# schematic.net
KiCad netlist of a schematic drawn in EasyEDA
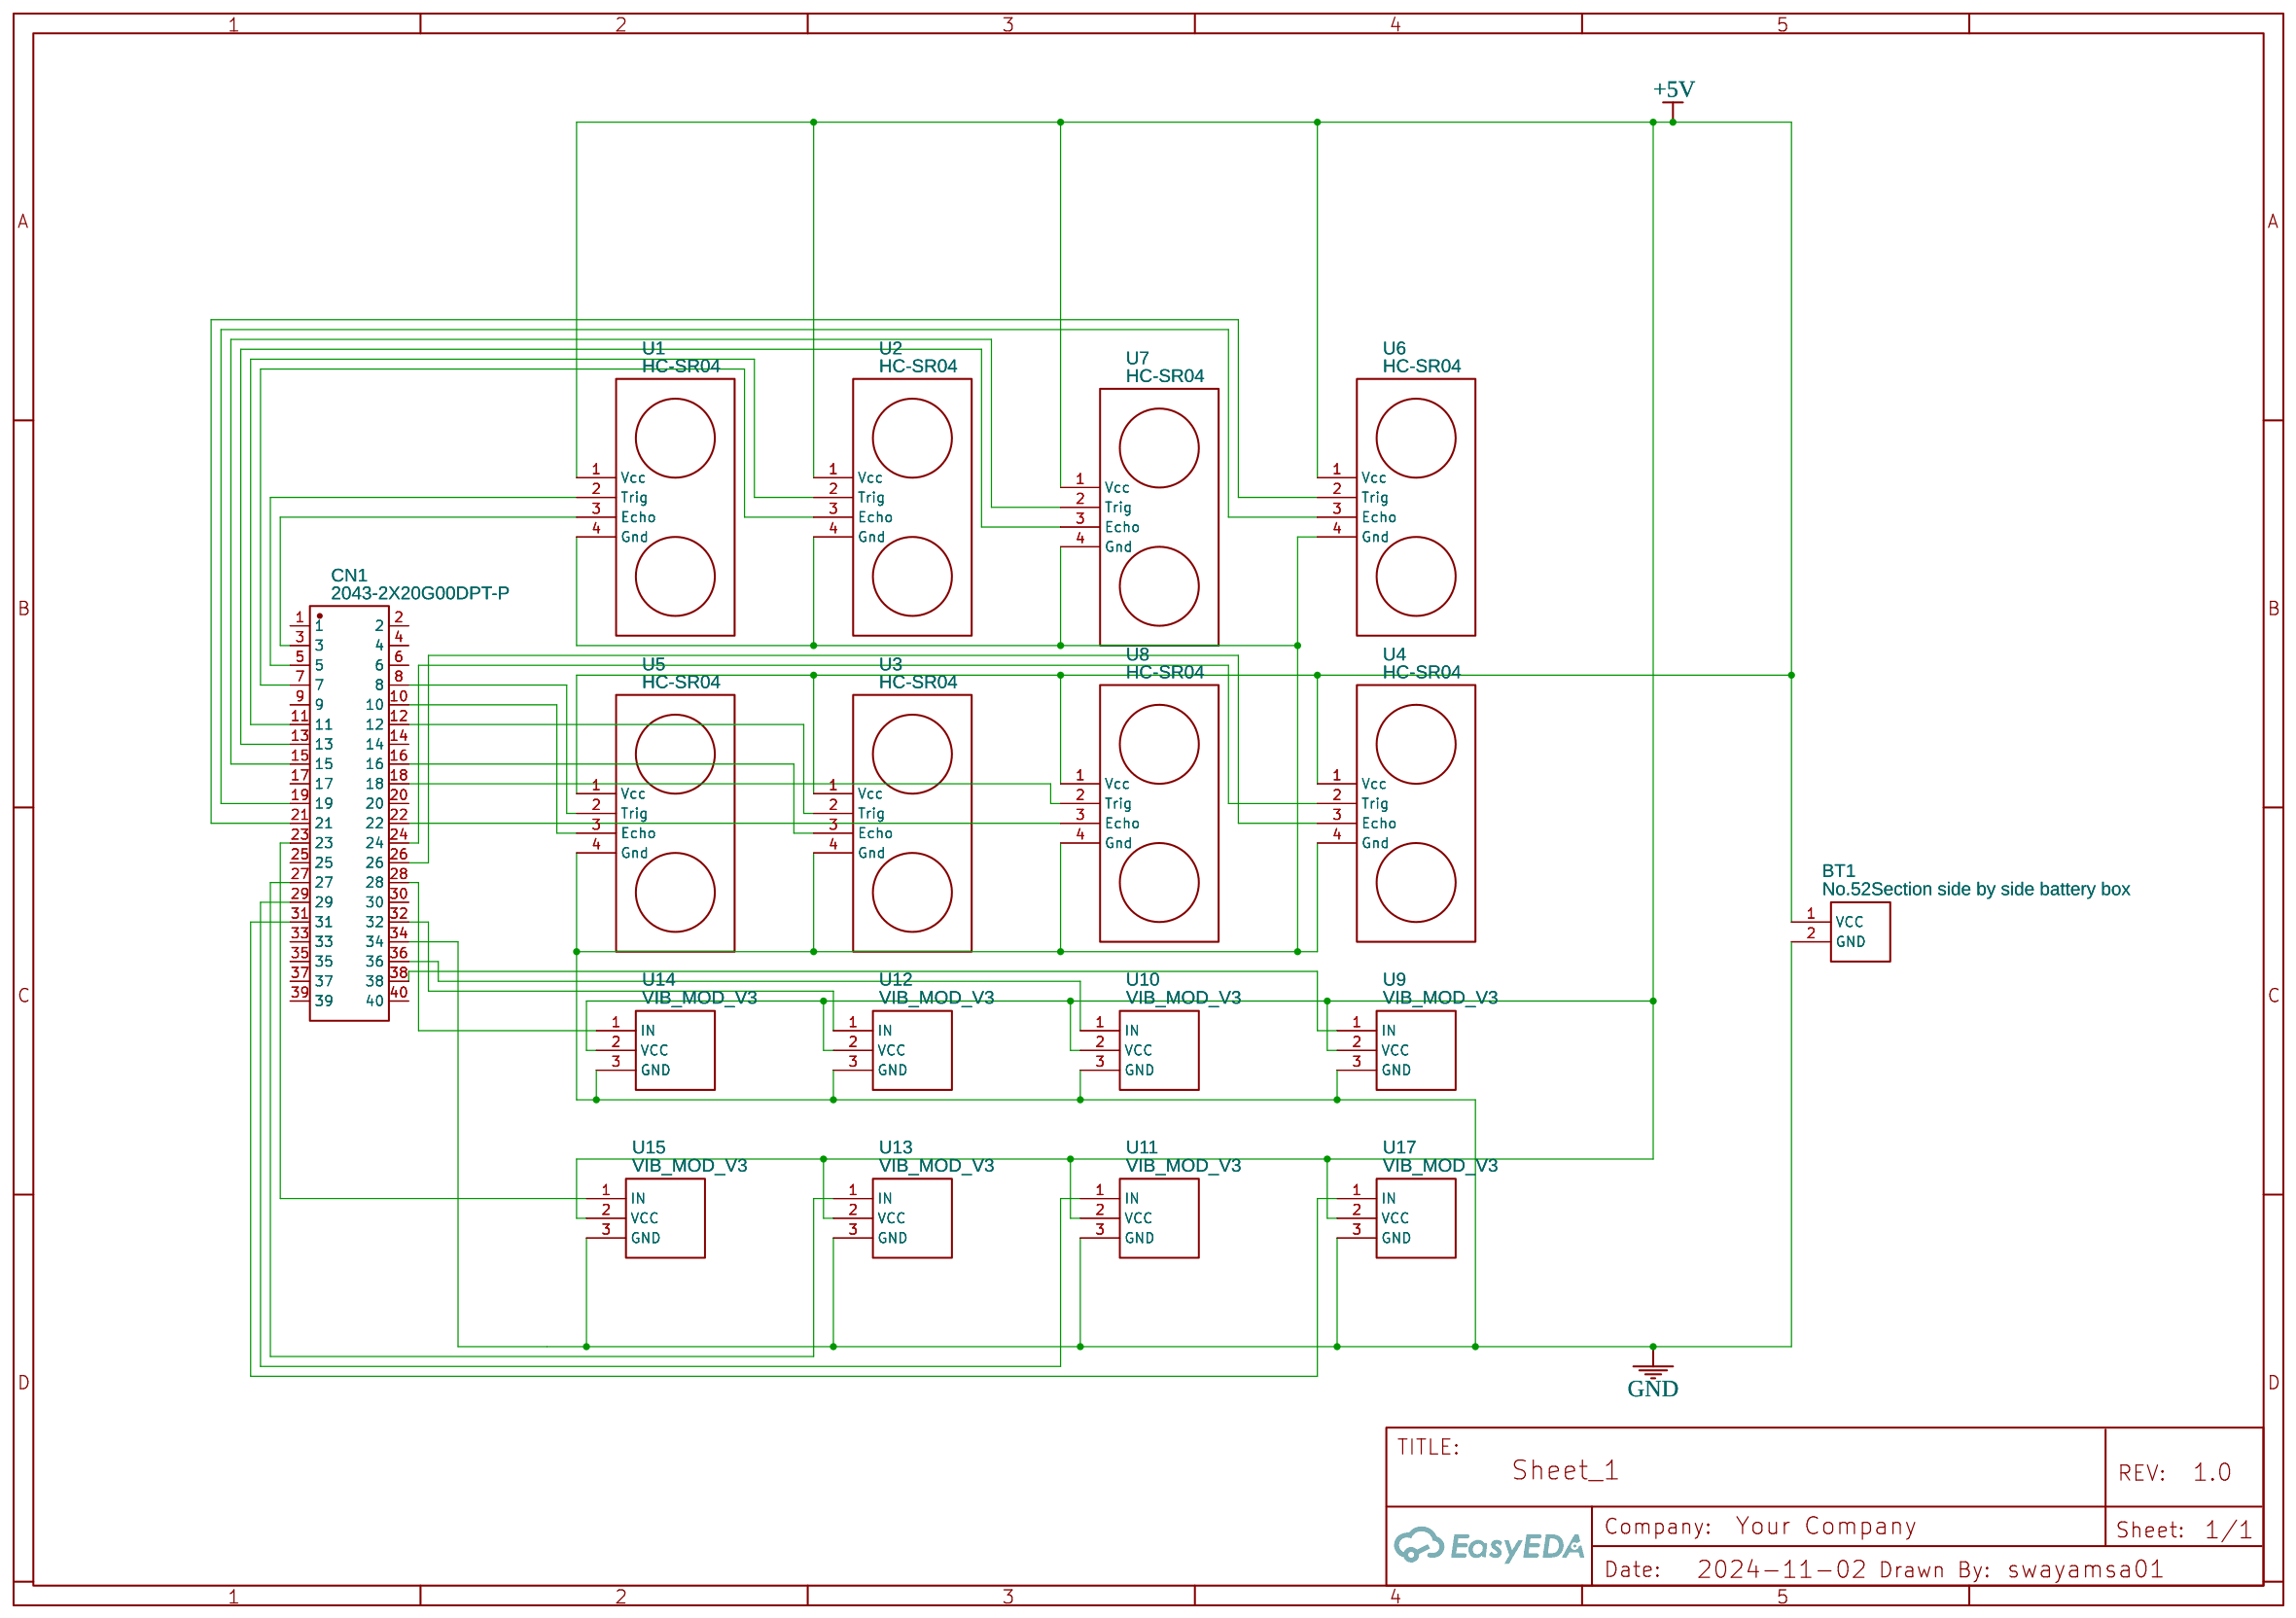
[diagram p0: schematic sheet]

(export (version "E")
  (design (tool "Eeschema 10.0.6"))
  (components
    (comp (ref "BT1")
      (value "No.52Section side by side battery box")
      (fields (field (name "Manufacturer Part") "五号2节并列电池盒") (field (name "Manufacturer") "国产"))
      (libsource (lib "") (part "No.52Section side by side battery box"))
    )
    (comp (ref "CN1") (value "2043-2X20G00DPT-P") (libsource (lib "") (part "2043-2X20G00DPT-P")))
    (comp (ref "U1") (value "HC-SR04") (libsource (lib "") (part "HC-SR04")))
    (comp (ref "U2") (value "HC-SR04") (libsource (lib "") (part "HC-SR04")))
    (comp (ref "U3") (value "HC-SR04") (libsource (lib "") (part "HC-SR04")))
    (comp (ref "U4") (value "HC-SR04") (libsource (lib "") (part "HC-SR04")))
    (comp (ref "U5") (value "HC-SR04") (libsource (lib "") (part "HC-SR04")))
    (comp (ref "U6") (value "HC-SR04") (libsource (lib "") (part "HC-SR04")))
    (comp (ref "U7") (value "HC-SR04") (libsource (lib "") (part "HC-SR04")))
    (comp (ref "U8") (value "HC-SR04") (libsource (lib "") (part "HC-SR04")))
    (comp (ref "U9") (value "VIB_MOD_V3") (libsource (lib "") (part "VIB_MOD_V3")))
    (comp (ref "U10") (value "VIB_MOD_V3") (libsource (lib "") (part "VIB_MOD_V3")))
    (comp (ref "U11") (value "VIB_MOD_V3") (libsource (lib "") (part "VIB_MOD_V3")))
    (comp (ref "U12") (value "VIB_MOD_V3") (libsource (lib "") (part "VIB_MOD_V3")))
    (comp (ref "U13") (value "VIB_MOD_V3") (libsource (lib "") (part "VIB_MOD_V3")))
    (comp (ref "U14") (value "VIB_MOD_V3") (libsource (lib "") (part "VIB_MOD_V3")))
    (comp (ref "U15") (value "VIB_MOD_V3") (libsource (lib "") (part "VIB_MOD_V3")))
    (comp (ref "U17") (value "VIB_MOD_V3") (libsource (lib "") (part "VIB_MOD_V3")))
  )
  (nets
    (net (code "1") (name "+5V") (class "Default")
      (node (ref "BT1") (pin "1") (pinfunction "VCC_1") (pintype "unspecified"))
      (node (ref "U1") (pin "1") (pinfunction "Vcc_1") (pintype "unspecified"))
      (node (ref "U10") (pin "2") (pinfunction "VCC_2") (pintype "unspecified"))
      (node (ref "U11") (pin "2") (pinfunction "VCC_2") (pintype "unspecified"))
      (node (ref "U12") (pin "2") (pinfunction "VCC_2") (pintype "unspecified"))
      (node (ref "U13") (pin "2") (pinfunction "VCC_2") (pintype "unspecified"))
      (node (ref "U14") (pin "2") (pinfunction "VCC_2") (pintype "unspecified"))
      (node (ref "U15") (pin "2") (pinfunction "VCC_2") (pintype "unspecified"))
      (node (ref "U17") (pin "2") (pinfunction "VCC_2") (pintype "unspecified"))
      (node (ref "U2") (pin "1") (pinfunction "Vcc_1") (pintype "unspecified"))
      (node (ref "U3") (pin "1") (pinfunction "Vcc_1") (pintype "unspecified"))
      (node (ref "U4") (pin "1") (pinfunction "Vcc_1") (pintype "unspecified"))
      (node (ref "U5") (pin "1") (pinfunction "Vcc_1") (pintype "unspecified"))
      (node (ref "U6") (pin "1") (pinfunction "Vcc_1") (pintype "unspecified"))
      (node (ref "U7") (pin "1") (pinfunction "Vcc_1") (pintype "unspecified"))
      (node (ref "U8") (pin "1") (pinfunction "Vcc_1") (pintype "unspecified"))
      (node (ref "U9") (pin "2") (pinfunction "VCC_2") (pintype "unspecified"))
    )
    (net (code "2") (name "GND") (class "Default")
      (node (ref "BT1") (pin "2") (pinfunction "GND_2") (pintype "unspecified"))
      (node (ref "CN1") (pin "34") (pinfunction "34_34") (pintype "unspecified"))
      (node (ref "U1") (pin "4") (pinfunction "Gnd_4") (pintype "unspecified"))
      (node (ref "U10") (pin "3") (pinfunction "GND_3") (pintype "unspecified"))
      (node (ref "U11") (pin "3") (pinfunction "GND_3") (pintype "unspecified"))
      (node (ref "U12") (pin "3") (pinfunction "GND_3") (pintype "unspecified"))
      (node (ref "U13") (pin "3") (pinfunction "GND_3") (pintype "unspecified"))
      (node (ref "U14") (pin "3") (pinfunction "GND_3") (pintype "unspecified"))
      (node (ref "U15") (pin "3") (pinfunction "GND_3") (pintype "unspecified"))
      (node (ref "U17") (pin "3") (pinfunction "GND_3") (pintype "unspecified"))
      (node (ref "U2") (pin "4") (pinfunction "Gnd_4") (pintype "unspecified"))
      (node (ref "U3") (pin "4") (pinfunction "Gnd_4") (pintype "unspecified"))
      (node (ref "U4") (pin "4") (pinfunction "Gnd_4") (pintype "unspecified"))
      (node (ref "U5") (pin "4") (pinfunction "Gnd_4") (pintype "unspecified"))
      (node (ref "U6") (pin "4") (pinfunction "Gnd_4") (pintype "unspecified"))
      (node (ref "U7") (pin "4") (pinfunction "Gnd_4") (pintype "unspecified"))
      (node (ref "U8") (pin "4") (pinfunction "Gnd_4") (pintype "unspecified"))
      (node (ref "U9") (pin "3") (pinfunction "GND_3") (pintype "unspecified"))
    )
    (net (code "3") (name "Net-(U1-Echo)") (class "Default")
      (node (ref "CN1") (pin "3") (pinfunction "3_3") (pintype "unspecified"))
      (node (ref "U1") (pin "3") (pinfunction "Echo_3") (pintype "unspecified"))
    )
    (net (code "4") (name "Net-(U1-Trig)") (class "Default")
      (node (ref "CN1") (pin "5") (pinfunction "5_5") (pintype "unspecified"))
      (node (ref "U1") (pin "2") (pinfunction "Trig_2") (pintype "unspecified"))
    )
    (net (code "5") (name "Net-(U2-Echo)") (class "Default")
      (node (ref "CN1") (pin "7") (pinfunction "7_7") (pintype "unspecified"))
      (node (ref "U2") (pin "3") (pinfunction "Echo_3") (pintype "unspecified"))
    )
    (net (code "6") (name "Net-(U2-Trig)") (class "Default")
      (node (ref "CN1") (pin "11") (pinfunction "11_11") (pintype "unspecified"))
      (node (ref "U2") (pin "2") (pinfunction "Trig_2") (pintype "unspecified"))
    )
    (net (code "7") (name "Net-(U3-Echo)") (class "Default")
      (node (ref "CN1") (pin "16") (pinfunction "16_16") (pintype "unspecified"))
      (node (ref "U3") (pin "3") (pinfunction "Echo_3") (pintype "unspecified"))
    )
    (net (code "8") (name "Net-(U3-Trig)") (class "Default")
      (node (ref "CN1") (pin "12") (pinfunction "12_12") (pintype "unspecified"))
      (node (ref "U3") (pin "2") (pinfunction "Trig_2") (pintype "unspecified"))
    )
    (net (code "9") (name "Net-(U4-Echo)") (class "Default")
      (node (ref "CN1") (pin "26") (pinfunction "26_26") (pintype "unspecified"))
      (node (ref "U4") (pin "3") (pinfunction "Echo_3") (pintype "unspecified"))
    )
    (net (code "10") (name "Net-(U4-Trig)") (class "Default")
      (node (ref "CN1") (pin "24") (pinfunction "24_24") (pintype "unspecified"))
      (node (ref "U4") (pin "2") (pinfunction "Trig_2") (pintype "unspecified"))
    )
    (net (code "11") (name "Net-(U5-Echo)") (class "Default")
      (node (ref "CN1") (pin "10") (pinfunction "10_10") (pintype "unspecified"))
      (node (ref "U5") (pin "3") (pinfunction "Echo_3") (pintype "unspecified"))
    )
    (net (code "12") (name "Net-(U5-Trig)") (class "Default")
      (node (ref "CN1") (pin "8") (pinfunction "8_8") (pintype "unspecified"))
      (node (ref "U5") (pin "2") (pinfunction "Trig_2") (pintype "unspecified"))
    )
    (net (code "13") (name "Net-(U6-Echo)") (class "Default")
      (node (ref "CN1") (pin "19") (pinfunction "19_19") (pintype "unspecified"))
      (node (ref "U6") (pin "3") (pinfunction "Echo_3") (pintype "unspecified"))
    )
    (net (code "14") (name "Net-(U6-Trig)") (class "Default")
      (node (ref "CN1") (pin "21") (pinfunction "21_21") (pintype "unspecified"))
      (node (ref "U6") (pin "2") (pinfunction "Trig_2") (pintype "unspecified"))
    )
    (net (code "15") (name "Net-(U7-Echo)") (class "Default")
      (node (ref "CN1") (pin "13") (pinfunction "13_13") (pintype "unspecified"))
      (node (ref "U7") (pin "3") (pinfunction "Echo_3") (pintype "unspecified"))
    )
    (net (code "16") (name "Net-(U7-Trig)") (class "Default")
      (node (ref "CN1") (pin "15") (pinfunction "15_15") (pintype "unspecified"))
      (node (ref "U7") (pin "2") (pinfunction "Trig_2") (pintype "unspecified"))
    )
    (net (code "17") (name "Net-(U8-Echo)") (class "Default")
      (node (ref "CN1") (pin "22") (pinfunction "22_22") (pintype "unspecified"))
      (node (ref "U8") (pin "3") (pinfunction "Echo_3") (pintype "unspecified"))
    )
    (net (code "18") (name "Net-(U8-Trig)") (class "Default")
      (node (ref "CN1") (pin "18") (pinfunction "18_18") (pintype "unspecified"))
      (node (ref "U8") (pin "2") (pinfunction "Trig_2") (pintype "unspecified"))
    )
    (net (code "19") (name "Net-(U9-IN)") (class "Default")
      (node (ref "CN1") (pin "38") (pinfunction "38_38") (pintype "unspecified"))
      (node (ref "U9") (pin "1") (pinfunction "IN_1") (pintype "unspecified"))
    )
    (net (code "20") (name "Net-(U10-IN)") (class "Default")
      (node (ref "CN1") (pin "36") (pinfunction "36_36") (pintype "unspecified"))
      (node (ref "U10") (pin "1") (pinfunction "IN_1") (pintype "unspecified"))
    )
    (net (code "21") (name "Net-(U11-IN)") (class "Default")
      (node (ref "CN1") (pin "29") (pinfunction "29_29") (pintype "unspecified"))
      (node (ref "U11") (pin "1") (pinfunction "IN_1") (pintype "unspecified"))
    )
    (net (code "22") (name "Net-(U12-IN)") (class "Default")
      (node (ref "CN1") (pin "32") (pinfunction "32_32") (pintype "unspecified"))
      (node (ref "U12") (pin "1") (pinfunction "IN_1") (pintype "unspecified"))
    )
    (net (code "23") (name "Net-(U13-IN)") (class "Default")
      (node (ref "CN1") (pin "27") (pinfunction "27_27") (pintype "unspecified"))
      (node (ref "U13") (pin "1") (pinfunction "IN_1") (pintype "unspecified"))
    )
    (net (code "24") (name "Net-(U14-IN)") (class "Default")
      (node (ref "CN1") (pin "28") (pinfunction "28_28") (pintype "unspecified"))
      (node (ref "U14") (pin "1") (pinfunction "IN_1") (pintype "unspecified"))
    )
    (net (code "25") (name "Net-(U15-IN)") (class "Default")
      (node (ref "CN1") (pin "23") (pinfunction "23_23") (pintype "unspecified"))
      (node (ref "U15") (pin "1") (pinfunction "IN_1") (pintype "unspecified"))
    )
    (net (code "26") (name "Net-(U17-IN)") (class "Default")
      (node (ref "CN1") (pin "31") (pinfunction "31_31") (pintype "unspecified"))
      (node (ref "U17") (pin "1") (pinfunction "IN_1") (pintype "unspecified"))
    )
    (net (code "27") (name "unconnected-(CN1-Pad1)") (class "Default")
      (node (ref "CN1") (pin "1") (pinfunction "1_1") (pintype "unspecified"))
    )
    (net (code "28") (name "unconnected-(CN1-Pad2)") (class "Default")
      (node (ref "CN1") (pin "2") (pinfunction "2_2") (pintype "unspecified"))
    )
    (net (code "29") (name "unconnected-(CN1-Pad4)") (class "Default")
      (node (ref "CN1") (pin "4") (pinfunction "4_4") (pintype "unspecified"))
    )
    (net (code "30") (name "unconnected-(CN1-Pad6)") (class "Default")
      (node (ref "CN1") (pin "6") (pinfunction "6_6") (pintype "unspecified"))
    )
    (net (code "31") (name "unconnected-(CN1-Pad9)") (class "Default")
      (node (ref "CN1") (pin "9") (pinfunction "9_9") (pintype "unspecified"))
    )
    (net (code "32") (name "unconnected-(CN1-Pad14)") (class "Default")
      (node (ref "CN1") (pin "14") (pinfunction "14_14") (pintype "unspecified"))
    )
    (net (code "33") (name "unconnected-(CN1-Pad17)") (class "Default")
      (node (ref "CN1") (pin "17") (pinfunction "17_17") (pintype "unspecified"))
    )
    (net (code "34") (name "unconnected-(CN1-Pad20)") (class "Default")
      (node (ref "CN1") (pin "20") (pinfunction "20_20") (pintype "unspecified"))
    )
    (net (code "35") (name "unconnected-(CN1-Pad25)") (class "Default")
      (node (ref "CN1") (pin "25") (pinfunction "25_25") (pintype "unspecified"))
    )
    (net (code "36") (name "unconnected-(CN1-Pad30)") (class "Default")
      (node (ref "CN1") (pin "30") (pinfunction "30_30") (pintype "unspecified"))
    )
    (net (code "37") (name "unconnected-(CN1-Pad33)") (class "Default")
      (node (ref "CN1") (pin "33") (pinfunction "33_33") (pintype "unspecified"))
    )
    (net (code "38") (name "unconnected-(CN1-Pad35)") (class "Default")
      (node (ref "CN1") (pin "35") (pinfunction "35_35") (pintype "unspecified"))
    )
    (net (code "39") (name "unconnected-(CN1-Pad37)") (class "Default")
      (node (ref "CN1") (pin "37") (pinfunction "37_37") (pintype "unspecified"))
    )
    (net (code "40") (name "unconnected-(CN1-Pad39)") (class "Default")
      (node (ref "CN1") (pin "39") (pinfunction "39_39") (pintype "unspecified"))
    )
    (net (code "41") (name "unconnected-(CN1-Pad40)") (class "Default")
      (node (ref "CN1") (pin "40") (pinfunction "40_40") (pintype "unspecified"))
    )
  )
)
